# SpeakEasy_POE.net
KiCad netlist of a schematic drawn in Altium Designer
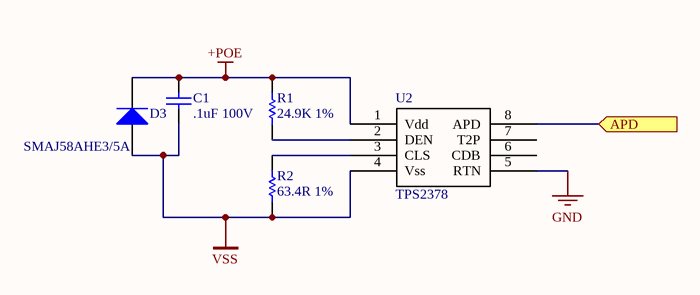
[diagram p0: SpeakEasy_POE.SchDoc]

(export (version "E")
  (design (tool "Eeschema 10.0.6"))
  (components
    (comp (ref "C1")
      (value ".1uF 100V")
      (footprint "CAPC0603(1608)100_L")
      (description "0.1µF ±10% 100V Ceramic Capacitor X7S 0603 (1608 Metric)")
      (libsource (lib "Altium Content Vault") (part "CAP_5"))
    )
    (comp (ref "D3")
      (value "SMAJ58AHE3/5A")
      (footprint "VISH-DO-214AC-2_M")
      (fields (field (name "MANUFACTURER") "Vishay Semiconductor"))
      (libsource (lib "Altium Content Vault") (part "VISH-K1A2-2"))
    )
    (comp (ref "R1")
      (value "24.9K 1%")
      (footprint "RESC0603(1608)_L")
      (description "0603 (1608 Metric) Chip Resistor")
      (libsource (lib "Altium Content Vault") (part "RES_3"))
    )
    (comp (ref "R2")
      (value "63.4R 1%")
      (footprint "RESC0603(1608)_L")
      (description "0603 (1608 Metric) Chip Resistor")
      (libsource (lib "Altium Content Vault") (part "RES_3"))
    )
    (comp (ref "U2")
      (value "TPS2378")
      (footprint "8SOPWR")
      (description "POE Manager IC")
      (libsource (lib "SpeakEasy") (part "TPS2378"))
    )
  )
  (nets
    (net (code "1") (name "+POE") (class "Default")
      (node (ref "C1") (pin "1") (pinfunction "1_1") (pintype "passive"))
      (node (ref "D3") (pin "1") (pinfunction "K_1") (pintype "passive"))
      (node (ref "R1") (pin "2") (pinfunction "2_2") (pintype "passive"))
      (node (ref "U2") (pin "1") (pinfunction "Vdd_1") (pintype "passive"))
    )
    (net (code "2") (name "/APD") (class "Default")
      (node (ref "U2") (pin "8") (pinfunction "APD_8") (pintype "passive"))
    )
    (net (code "3") (name "GND") (class "Default")
      (node (ref "U2") (pin "5") (pinfunction "RTN_5") (pintype "passive"))
    )
    (net (code "4") (name "Net-(U2-CLS)") (class "Default")
      (node (ref "R2") (pin "2") (pinfunction "2_2") (pintype "passive"))
      (node (ref "U2") (pin "3") (pinfunction "CLS_3") (pintype "passive"))
    )
    (net (code "5") (name "Net-(U2-DEN)") (class "Default")
      (node (ref "R1") (pin "1") (pinfunction "1_1") (pintype "passive"))
      (node (ref "U2") (pin "2") (pinfunction "DEN_2") (pintype "passive"))
    )
    (net (code "6") (name "VSS") (class "Default")
      (node (ref "C1") (pin "2") (pinfunction "2_2") (pintype "passive"))
      (node (ref "D3") (pin "2") (pinfunction "A_2") (pintype "passive"))
      (node (ref "R2") (pin "1") (pinfunction "1_1") (pintype "passive"))
      (node (ref "U2") (pin "4") (pinfunction "Vss_4") (pintype "passive"))
    )
    (net (code "7") (name "unconnected-(U2-CDB-Pad6)") (class "Default")
      (node (ref "U2") (pin "6") (pinfunction "CDB_6") (pintype "passive"))
    )
    (net (code "8") (name "unconnected-(U2-T2P-Pad7)") (class "Default")
      (node (ref "U2") (pin "7") (pinfunction "T2P_7") (pintype "passive"))
    )
  )
)
